# A502X.net
KiCad netlist of a schematic drawn in EAGLE
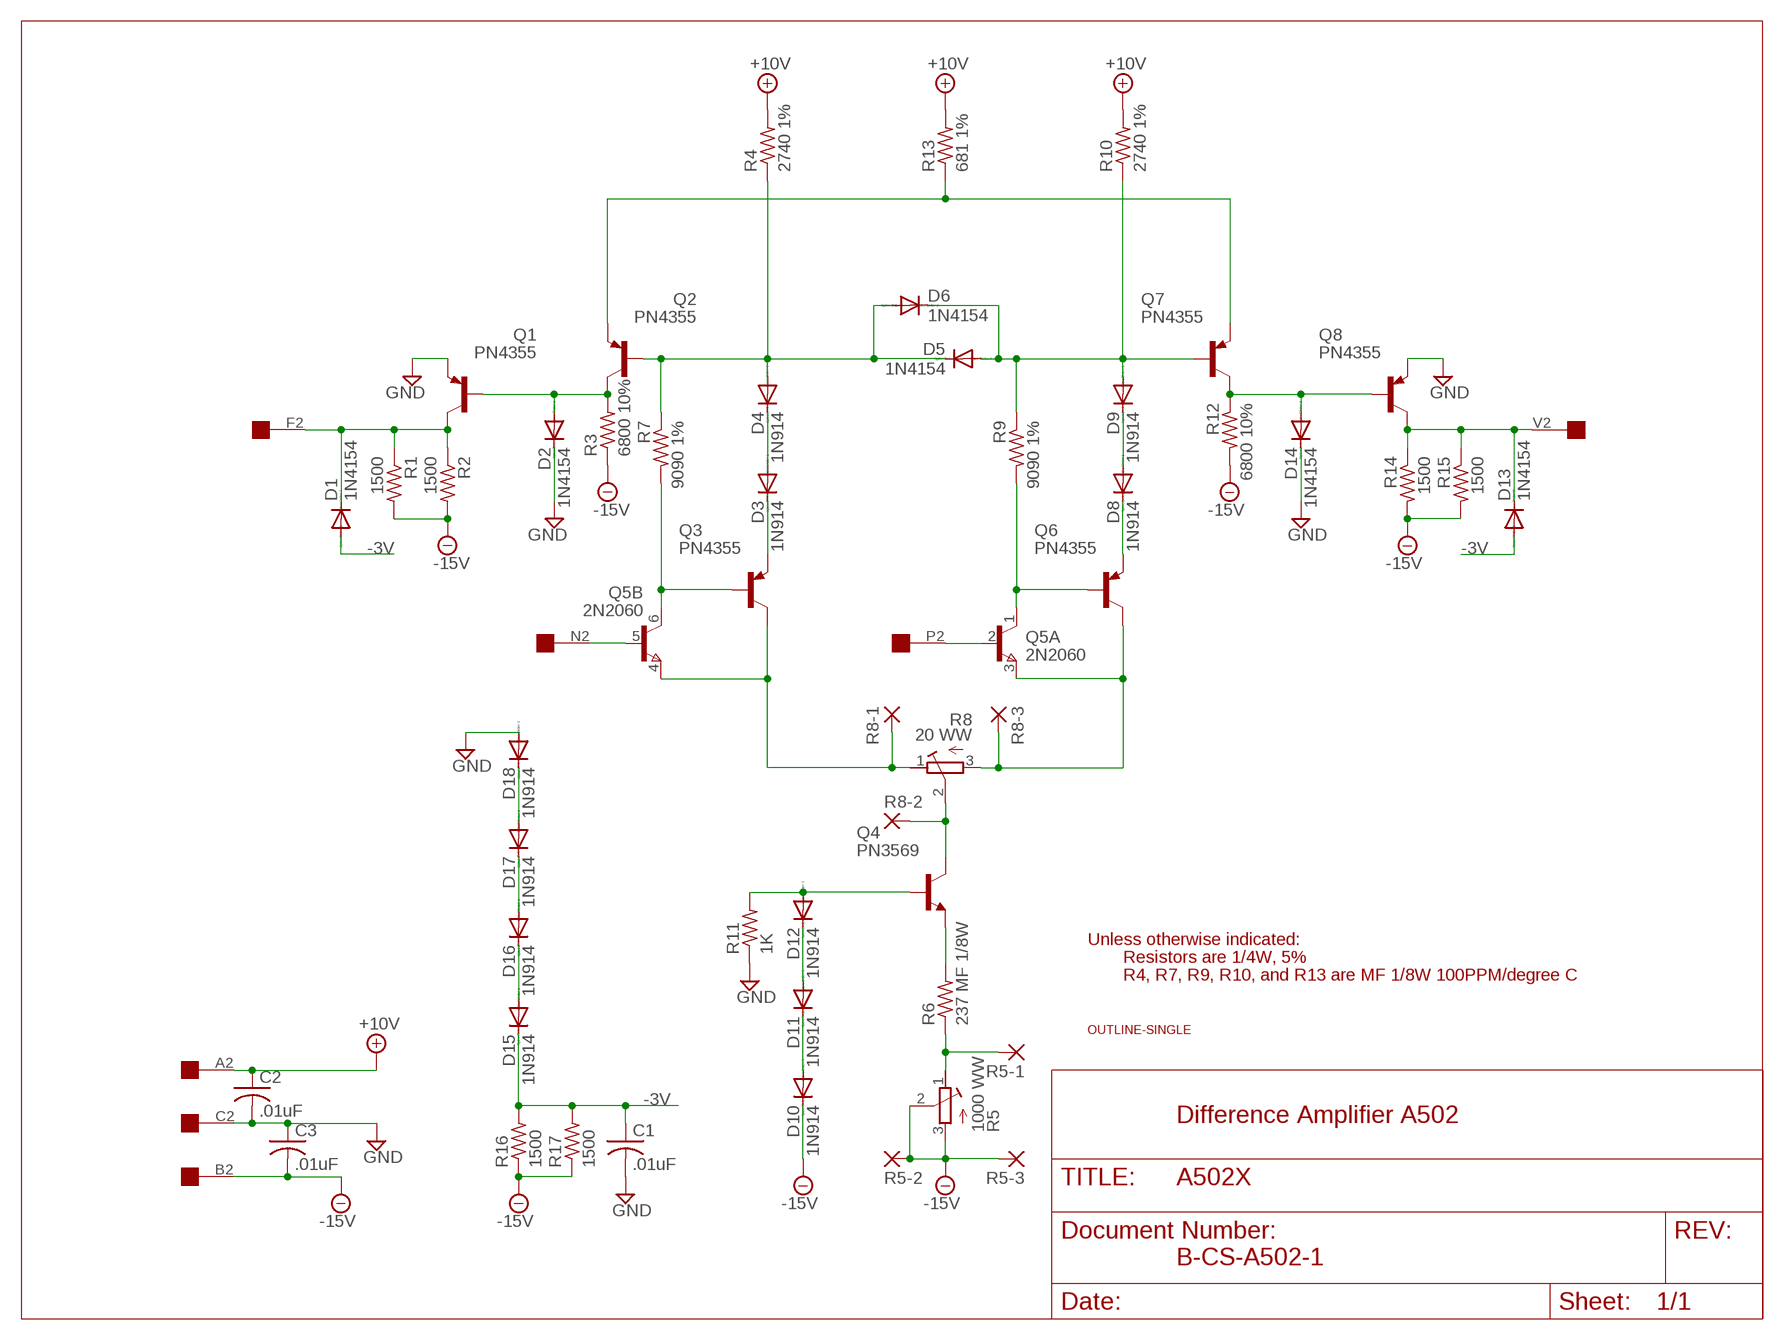
[diagram p0: schematic, sheet 1]

(export (version "E")
  (design (tool "Eeschema 10.0.6"))
  (components
    (comp (ref "C1")
      (value ".01uF")
      (footprint "eagle-import:C050-025X075")
      (libsource (lib "eagle-import") (part "C-US050-025X075"))
    )
    (comp (ref "C2")
      (value ".01uF")
      (footprint "eagle-import:C050-025X075")
      (libsource (lib "eagle-import") (part "C-US050-025X075"))
    )
    (comp (ref "C3")
      (value ".01uF")
      (footprint "eagle-import:C050-025X075")
      (libsource (lib "eagle-import") (part "C-US050-025X075"))
    )
    (comp (ref "D1")
      (value "1N4154")
      (footprint "eagle-import:DO35-10")
      (libsource (lib "eagle-import") (part "1N4148DO35-10"))
    )
    (comp (ref "D2")
      (value "1N4154")
      (footprint "eagle-import:DO35-10")
      (libsource (lib "eagle-import") (part "1N4148DO35-10"))
    )
    (comp (ref "D3")
      (value "1N914")
      (footprint "eagle-import:DO35-10")
      (libsource (lib "eagle-import") (part "1N4148DO35-10"))
    )
    (comp (ref "D4")
      (value "1N914")
      (footprint "eagle-import:DO35-10")
      (libsource (lib "eagle-import") (part "1N4148DO35-10"))
    )
    (comp (ref "D5")
      (value "1N4154")
      (footprint "eagle-import:DO35-10")
      (libsource (lib "eagle-import") (part "1N4148DO35-10"))
    )
    (comp (ref "D6")
      (value "1N4154")
      (footprint "eagle-import:DO35-10")
      (libsource (lib "eagle-import") (part "1N4148DO35-10"))
    )
    (comp (ref "D8")
      (value "1N914")
      (footprint "eagle-import:DO35-10")
      (libsource (lib "eagle-import") (part "1N4148DO35-10"))
    )
    (comp (ref "D9")
      (value "1N914")
      (footprint "eagle-import:DO35-10")
      (libsource (lib "eagle-import") (part "1N4148DO35-10"))
    )
    (comp (ref "D10")
      (value "1N914")
      (footprint "eagle-import:DO35-10")
      (libsource (lib "eagle-import") (part "1N4148DO35-10"))
    )
    (comp (ref "D11")
      (value "1N914")
      (footprint "eagle-import:DO35-10")
      (libsource (lib "eagle-import") (part "1N4148DO35-10"))
    )
    (comp (ref "D12")
      (value "1N914")
      (footprint "eagle-import:DO35-10")
      (libsource (lib "eagle-import") (part "1N4148DO35-10"))
    )
    (comp (ref "D13")
      (value "1N4154")
      (footprint "eagle-import:DO35-10")
      (libsource (lib "eagle-import") (part "1N4148DO35-10"))
    )
    (comp (ref "D14")
      (value "1N4154")
      (footprint "eagle-import:DO35-10")
      (libsource (lib "eagle-import") (part "1N4148DO35-10"))
    )
    (comp (ref "D15")
      (value "1N914")
      (footprint "eagle-import:DO35-10")
      (libsource (lib "eagle-import") (part "1N4148DO35-10"))
    )
    (comp (ref "D16")
      (value "1N914")
      (footprint "eagle-import:DO35-10")
      (libsource (lib "eagle-import") (part "1N4148DO35-10"))
    )
    (comp (ref "D17")
      (value "1N914")
      (footprint "eagle-import:DO35-10")
      (libsource (lib "eagle-import") (part "1N4148DO35-10"))
    )
    (comp (ref "D18")
      (value "1N914")
      (footprint "eagle-import:DO35-10")
      (libsource (lib "eagle-import") (part "1N4148DO35-10"))
    )
    (comp (ref "Q1")
      (value "PN4355")
      (footprint "eagle-import:TO39")
      (libsource (lib "eagle-import") (part "2N2904A"))
    )
    (comp (ref "Q2")
      (value "PN4355")
      (footprint "eagle-import:TO39")
      (libsource (lib "eagle-import") (part "2N2904A"))
    )
    (comp (ref "Q3")
      (value "PN4355")
      (footprint "eagle-import:TO39")
      (libsource (lib "eagle-import") (part "2N2904A"))
    )
    (comp (ref "Q4")
      (value "PN3569")
      (footprint "eagle-import:TO5")
      (libsource (lib "eagle-import") (part "2N2219"))
    )
    (comp (ref "Q5")
      (value "2N2060")
      (footprint "eagle-import:TO78")
      (libsource (lib "eagle-import") (part "MAT-02H"))
    )
    (comp (ref "Q6")
      (value "PN4355")
      (footprint "eagle-import:TO39")
      (libsource (lib "eagle-import") (part "2N2904A"))
    )
    (comp (ref "Q7")
      (value "PN4355")
      (footprint "eagle-import:TO39")
      (libsource (lib "eagle-import") (part "2N2904A"))
    )
    (comp (ref "Q8")
      (value "PN4355")
      (footprint "eagle-import:TO39")
      (libsource (lib "eagle-import") (part "2N2904A"))
    )
    (comp (ref "R1")
      (value "1500")
      (footprint "eagle-import:0207_10")
      (libsource (lib "eagle-import") (part "R-US_0207/10"))
    )
    (comp (ref "R2")
      (value "1500")
      (footprint "eagle-import:0207_10")
      (libsource (lib "eagle-import") (part "R-US_0207/10"))
    )
    (comp (ref "R3")
      (value "6800 10%")
      (footprint "eagle-import:0207_10")
      (libsource (lib "eagle-import") (part "R-US_0207/10"))
    )
    (comp (ref "R4")
      (value "2740 1%")
      (footprint "eagle-import:0207_15")
      (libsource (lib "eagle-import") (part "R-US_0207/15"))
    )
    (comp (ref "R5")
      (value "1000 WW")
      (footprint "eagle-import:3006Y")
      (libsource (lib "eagle-import") (part "275P"))
    )
    (comp (ref "R5-1")
      (value "2,54/0,8")
      (footprint "eagle-import:2,54_0,8")
      (libsource (lib "eagle-import") (part "2,54/0,8"))
    )
    (comp (ref "R5-2")
      (value "2,54/0,8")
      (footprint "eagle-import:2,54_0,8")
      (libsource (lib "eagle-import") (part "2,54/0,8"))
    )
    (comp (ref "R5-3")
      (value "2,54/0,8")
      (footprint "eagle-import:2,54_0,8")
      (libsource (lib "eagle-import") (part "2,54/0,8"))
    )
    (comp (ref "R6")
      (value "237 MF 1/8W")
      (footprint "eagle-import:0207_15")
      (libsource (lib "eagle-import") (part "R-US_0207/15"))
    )
    (comp (ref "R7")
      (value "9090 1%")
      (footprint "eagle-import:0207_15")
      (libsource (lib "eagle-import") (part "R-US_0207/15"))
    )
    (comp (ref "R8")
      (value "20 WW")
      (footprint "eagle-import:3006Y")
      (libsource (lib "eagle-import") (part "275P"))
    )
    (comp (ref "R8-1")
      (value "2,54/0,8")
      (footprint "eagle-import:2,54_0,8")
      (libsource (lib "eagle-import") (part "2,54/0,8"))
    )
    (comp (ref "R8-2")
      (value "2,54/0,8")
      (footprint "eagle-import:2,54_0,8")
      (libsource (lib "eagle-import") (part "2,54/0,8"))
    )
    (comp (ref "R8-3")
      (value "2,54/0,8")
      (footprint "eagle-import:2,54_0,8")
      (libsource (lib "eagle-import") (part "2,54/0,8"))
    )
    (comp (ref "R9")
      (value "9090 1%")
      (footprint "eagle-import:0207_15")
      (libsource (lib "eagle-import") (part "R-US_0207/15"))
    )
    (comp (ref "R10")
      (value "2740 1%")
      (footprint "eagle-import:0207_15")
      (libsource (lib "eagle-import") (part "R-US_0207/15"))
    )
    (comp (ref "R11")
      (value "1K")
      (footprint "eagle-import:0207_10")
      (libsource (lib "eagle-import") (part "R-US_0207/10"))
    )
    (comp (ref "R12")
      (value "6800 10%")
      (footprint "eagle-import:0207_10")
      (libsource (lib "eagle-import") (part "R-US_0207/10"))
    )
    (comp (ref "R13")
      (value "681 1%")
      (footprint "eagle-import:0207_15")
      (libsource (lib "eagle-import") (part "R-US_0207/15"))
    )
    (comp (ref "R14")
      (value "1500")
      (footprint "eagle-import:0207_10")
      (libsource (lib "eagle-import") (part "R-US_0207/10"))
    )
    (comp (ref "R15")
      (value "1500")
      (footprint "eagle-import:0207_10")
      (libsource (lib "eagle-import") (part "R-US_0207/10"))
    )
    (comp (ref "R16")
      (value "1500")
      (footprint "eagle-import:0207_10")
      (libsource (lib "eagle-import") (part "R-US_0207/10"))
    )
    (comp (ref "R17")
      (value "1500")
      (footprint "eagle-import:0207_10")
      (libsource (lib "eagle-import") (part "R-US_0207/10"))
    )
    (comp (ref "U$2")
      (value "OUTLINE-SINGLE")
      (footprint "eagle-import:SINGLE")
      (libsource (lib "eagle-import") (part "OUTLINE-SINGLE"))
    )
    (comp (ref "U$3")
      (value "EDGE-1")
      (footprint "eagle-import:EDGE-CON1")
      (libsource (lib "eagle-import") (part "EDGE-1"))
    )
  )
  (nets
    (net (code "1") (name "+10V") (class "Default")
      (node (ref "C2") (pin "1") (pinfunction "1_1") (pintype "passive"))
      (node (ref "R10") (pin "2") (pinfunction "2_2") (pintype "passive"))
      (node (ref "R13") (pin "2") (pinfunction "2_2") (pintype "passive"))
      (node (ref "R4") (pin "2") (pinfunction "2_2") (pintype "passive"))
      (node (ref "U$3") (pin "A2") (pinfunction "1_A2") (pintype "bidirectional"))
    )
    (net (code "2") (name "-15V") (class "Default")
      (node (ref "C3") (pin "2") (pinfunction "2_2") (pintype "passive"))
      (node (ref "D10") (pin "C") (pinfunction "C_C") (pintype "passive"))
      (node (ref "R1") (pin "2") (pinfunction "2_2") (pintype "passive"))
      (node (ref "R12") (pin "2") (pinfunction "2_2") (pintype "passive"))
      (node (ref "R14") (pin "2") (pinfunction "2_2") (pintype "passive"))
      (node (ref "R15") (pin "2") (pinfunction "2_2") (pintype "passive"))
      (node (ref "R16") (pin "1") (pinfunction "1_1") (pintype "passive"))
      (node (ref "R17") (pin "1") (pinfunction "1_1") (pintype "passive"))
      (node (ref "R2") (pin "2") (pinfunction "2_2") (pintype "passive"))
      (node (ref "R3") (pin "1") (pinfunction "1_1") (pintype "passive"))
      (node (ref "R5") (pin "2") (pinfunction "S_2") (pintype "passive"))
      (node (ref "R5") (pin "3") (pinfunction "E_3") (pintype "passive"))
      (node (ref "R5-2") (pin "1") (pinfunction "P_1") (pintype "passive"))
      (node (ref "R5-3") (pin "1") (pinfunction "P_1") (pintype "passive"))
      (node (ref "U$3") (pin "B2") (pinfunction "1_B2") (pintype "bidirectional"))
    )
    (net (code "3") (name "/-3V") (class "Default")
      (node (ref "C1") (pin "1") (pinfunction "1_1") (pintype "passive"))
      (node (ref "D1") (pin "A") (pinfunction "A_A") (pintype "passive"))
      (node (ref "D13") (pin "A") (pinfunction "A_A") (pintype "passive"))
      (node (ref "D15") (pin "C") (pinfunction "C_C") (pintype "passive"))
      (node (ref "R16") (pin "2") (pinfunction "2_2") (pintype "passive"))
      (node (ref "R17") (pin "2") (pinfunction "2_2") (pintype "passive"))
    )
    (net (code "4") (name "GND") (class "Default")
      (node (ref "C1") (pin "2") (pinfunction "2_2") (pintype "passive"))
      (node (ref "C2") (pin "2") (pinfunction "2_2") (pintype "passive"))
      (node (ref "C3") (pin "1") (pinfunction "1_1") (pintype "passive"))
      (node (ref "D14") (pin "C") (pinfunction "C_C") (pintype "passive"))
      (node (ref "D18") (pin "A") (pinfunction "A_A") (pintype "passive"))
      (node (ref "D2") (pin "C") (pinfunction "C_C") (pintype "passive"))
      (node (ref "Q1") (pin "1") (pinfunction "E_1") (pintype "passive"))
      (node (ref "Q8") (pin "1") (pinfunction "E_1") (pintype "passive"))
      (node (ref "R11") (pin "1") (pinfunction "1_1") (pintype "passive"))
      (node (ref "U$3") (pin "C2") (pinfunction "1_C2") (pintype "bidirectional"))
    )
    (net (code "5") (name "Net-(D3-PadA)") (class "Default")
      (node (ref "D3") (pin "A") (pinfunction "A_A") (pintype "passive"))
      (node (ref "D4") (pin "C") (pinfunction "C_C") (pintype "passive"))
    )
    (net (code "6") (name "Net-(D8-PadA)") (class "Default")
      (node (ref "D8") (pin "A") (pinfunction "A_A") (pintype "passive"))
      (node (ref "D9") (pin "C") (pinfunction "C_C") (pintype "passive"))
    )
    (net (code "7") (name "Net-(D10-PadA)") (class "Default")
      (node (ref "D10") (pin "A") (pinfunction "A_A") (pintype "passive"))
      (node (ref "D11") (pin "C") (pinfunction "C_C") (pintype "passive"))
    )
    (net (code "8") (name "Net-(D11-PadA)") (class "Default")
      (node (ref "D11") (pin "A") (pinfunction "A_A") (pintype "passive"))
      (node (ref "D12") (pin "C") (pinfunction "C_C") (pintype "passive"))
    )
    (net (code "9") (name "Net-(D15-PadA)") (class "Default")
      (node (ref "D15") (pin "A") (pinfunction "A_A") (pintype "passive"))
      (node (ref "D16") (pin "C") (pinfunction "C_C") (pintype "passive"))
    )
    (net (code "10") (name "Net-(D16-PadA)") (class "Default")
      (node (ref "D16") (pin "A") (pinfunction "A_A") (pintype "passive"))
      (node (ref "D17") (pin "C") (pinfunction "C_C") (pintype "passive"))
    )
    (net (code "11") (name "Net-(D17-PadA)") (class "Default")
      (node (ref "D17") (pin "A") (pinfunction "A_A") (pintype "passive"))
      (node (ref "D18") (pin "C") (pinfunction "C_C") (pintype "passive"))
    )
    (net (code "12") (name "Net-(Q1-B)") (class "Default")
      (node (ref "D2") (pin "A") (pinfunction "A_A") (pintype "passive"))
      (node (ref "Q1") (pin "2") (pinfunction "B_2") (pintype "passive"))
      (node (ref "Q2") (pin "3") (pinfunction "C_3") (pintype "passive"))
      (node (ref "R3") (pin "2") (pinfunction "2_2") (pintype "passive"))
    )
    (net (code "13") (name "Net-(Q1-C)") (class "Default")
      (node (ref "D1") (pin "C") (pinfunction "C_C") (pintype "passive"))
      (node (ref "Q1") (pin "3") (pinfunction "C_3") (pintype "passive"))
      (node (ref "R1") (pin "1") (pinfunction "1_1") (pintype "passive"))
      (node (ref "R2") (pin "1") (pinfunction "1_1") (pintype "passive"))
      (node (ref "U$3") (pin "F2") (pinfunction "1_F2") (pintype "bidirectional"))
    )
    (net (code "14") (name "Net-(Q2-B)") (class "Default")
      (node (ref "D4") (pin "A") (pinfunction "A_A") (pintype "passive"))
      (node (ref "D5") (pin "C") (pinfunction "C_C") (pintype "passive"))
      (node (ref "D6") (pin "A") (pinfunction "A_A") (pintype "passive"))
      (node (ref "Q2") (pin "2") (pinfunction "B_2") (pintype "passive"))
      (node (ref "R4") (pin "1") (pinfunction "1_1") (pintype "passive"))
      (node (ref "R7") (pin "1") (pinfunction "1_1") (pintype "passive"))
    )
    (net (code "15") (name "Net-(Q2-E)") (class "Default")
      (node (ref "Q2") (pin "1") (pinfunction "E_1") (pintype "passive"))
      (node (ref "Q7") (pin "1") (pinfunction "E_1") (pintype "passive"))
      (node (ref "R13") (pin "1") (pinfunction "1_1") (pintype "passive"))
    )
    (net (code "16") (name "Net-(Q3-B)") (class "Default")
      (node (ref "Q3") (pin "2") (pinfunction "B_2") (pintype "passive"))
      (node (ref "Q5") (pin "6") (pinfunction "C_6") (pintype "passive"))
      (node (ref "R7") (pin "2") (pinfunction "2_2") (pintype "passive"))
    )
    (net (code "17") (name "Net-(Q3-C)") (class "Default")
      (node (ref "Q3") (pin "3") (pinfunction "C_3") (pintype "passive"))
      (node (ref "Q5") (pin "4") (pinfunction "E_4") (pintype "passive"))
      (node (ref "R8") (pin "1") (pinfunction "A_1") (pintype "passive"))
      (node (ref "R8-1") (pin "1") (pinfunction "P_1") (pintype "passive"))
    )
    (net (code "18") (name "Net-(Q3-E)") (class "Default")
      (node (ref "D3") (pin "C") (pinfunction "C_C") (pintype "passive"))
      (node (ref "Q3") (pin "1") (pinfunction "E_1") (pintype "passive"))
    )
    (net (code "19") (name "Net-(Q4-B)") (class "Default")
      (node (ref "D12") (pin "A") (pinfunction "A_A") (pintype "passive"))
      (node (ref "Q4") (pin "2") (pinfunction "B_2") (pintype "passive"))
      (node (ref "R11") (pin "2") (pinfunction "2_2") (pintype "passive"))
    )
    (net (code "20") (name "Net-(Q4-C)") (class "Default")
      (node (ref "Q4") (pin "3") (pinfunction "C_3") (pintype "passive"))
      (node (ref "R8") (pin "2") (pinfunction "S_2") (pintype "passive"))
      (node (ref "R8-2") (pin "1") (pinfunction "P_1") (pintype "passive"))
    )
    (net (code "21") (name "Net-(Q4-E)") (class "Default")
      (node (ref "Q4") (pin "1") (pinfunction "E_1") (pintype "passive"))
      (node (ref "R6") (pin "2") (pinfunction "2_2") (pintype "passive"))
    )
    (net (code "22") (name "Net-(Q5A-B)") (class "Default")
      (node (ref "Q5") (pin "2") (pinfunction "B_2") (pintype "passive"))
      (node (ref "U$3") (pin "P2") (pinfunction "1_P2") (pintype "bidirectional"))
    )
    (net (code "23") (name "Net-(Q5A-C)") (class "Default")
      (node (ref "Q5") (pin "1") (pinfunction "C_1") (pintype "passive"))
      (node (ref "Q6") (pin "2") (pinfunction "B_2") (pintype "passive"))
      (node (ref "R9") (pin "2") (pinfunction "2_2") (pintype "passive"))
    )
    (net (code "24") (name "Net-(Q5A-E)") (class "Default")
      (node (ref "Q5") (pin "3") (pinfunction "E_3") (pintype "passive"))
      (node (ref "Q6") (pin "3") (pinfunction "C_3") (pintype "passive"))
      (node (ref "R8") (pin "3") (pinfunction "E_3") (pintype "passive"))
      (node (ref "R8-3") (pin "1") (pinfunction "P_1") (pintype "passive"))
    )
    (net (code "25") (name "Net-(Q5B-B)") (class "Default")
      (node (ref "Q5") (pin "5") (pinfunction "B_5") (pintype "passive"))
      (node (ref "U$3") (pin "N2") (pinfunction "1_N2") (pintype "bidirectional"))
    )
    (net (code "26") (name "Net-(Q6-E)") (class "Default")
      (node (ref "D8") (pin "C") (pinfunction "C_C") (pintype "passive"))
      (node (ref "Q6") (pin "1") (pinfunction "E_1") (pintype "passive"))
    )
    (net (code "27") (name "Net-(Q7-B)") (class "Default")
      (node (ref "D5") (pin "A") (pinfunction "A_A") (pintype "passive"))
      (node (ref "D6") (pin "C") (pinfunction "C_C") (pintype "passive"))
      (node (ref "D9") (pin "A") (pinfunction "A_A") (pintype "passive"))
      (node (ref "Q7") (pin "2") (pinfunction "B_2") (pintype "passive"))
      (node (ref "R10") (pin "1") (pinfunction "1_1") (pintype "passive"))
      (node (ref "R9") (pin "1") (pinfunction "1_1") (pintype "passive"))
    )
    (net (code "28") (name "Net-(Q7-C)") (class "Default")
      (node (ref "D14") (pin "A") (pinfunction "A_A") (pintype "passive"))
      (node (ref "Q7") (pin "3") (pinfunction "C_3") (pintype "passive"))
      (node (ref "Q8") (pin "2") (pinfunction "B_2") (pintype "passive"))
      (node (ref "R12") (pin "1") (pinfunction "1_1") (pintype "passive"))
    )
    (net (code "29") (name "Net-(Q8-C)") (class "Default")
      (node (ref "D13") (pin "C") (pinfunction "C_C") (pintype "passive"))
      (node (ref "Q8") (pin "3") (pinfunction "C_3") (pintype "passive"))
      (node (ref "R14") (pin "1") (pinfunction "1_1") (pintype "passive"))
      (node (ref "R15") (pin "1") (pinfunction "1_1") (pintype "passive"))
      (node (ref "U$3") (pin "V2") (pinfunction "1_V2") (pintype "bidirectional"))
    )
    (net (code "30") (name "Net-(R5-1-P)") (class "Default")
      (node (ref "R5") (pin "1") (pinfunction "A_1") (pintype "passive"))
      (node (ref "R5-1") (pin "1") (pinfunction "P_1") (pintype "passive"))
      (node (ref "R6") (pin "1") (pinfunction "1_1") (pintype "passive"))
    )
  )
)
